# fri3d_badge_2016.net
KiCad netlist of a schematic drawn in EAGLE
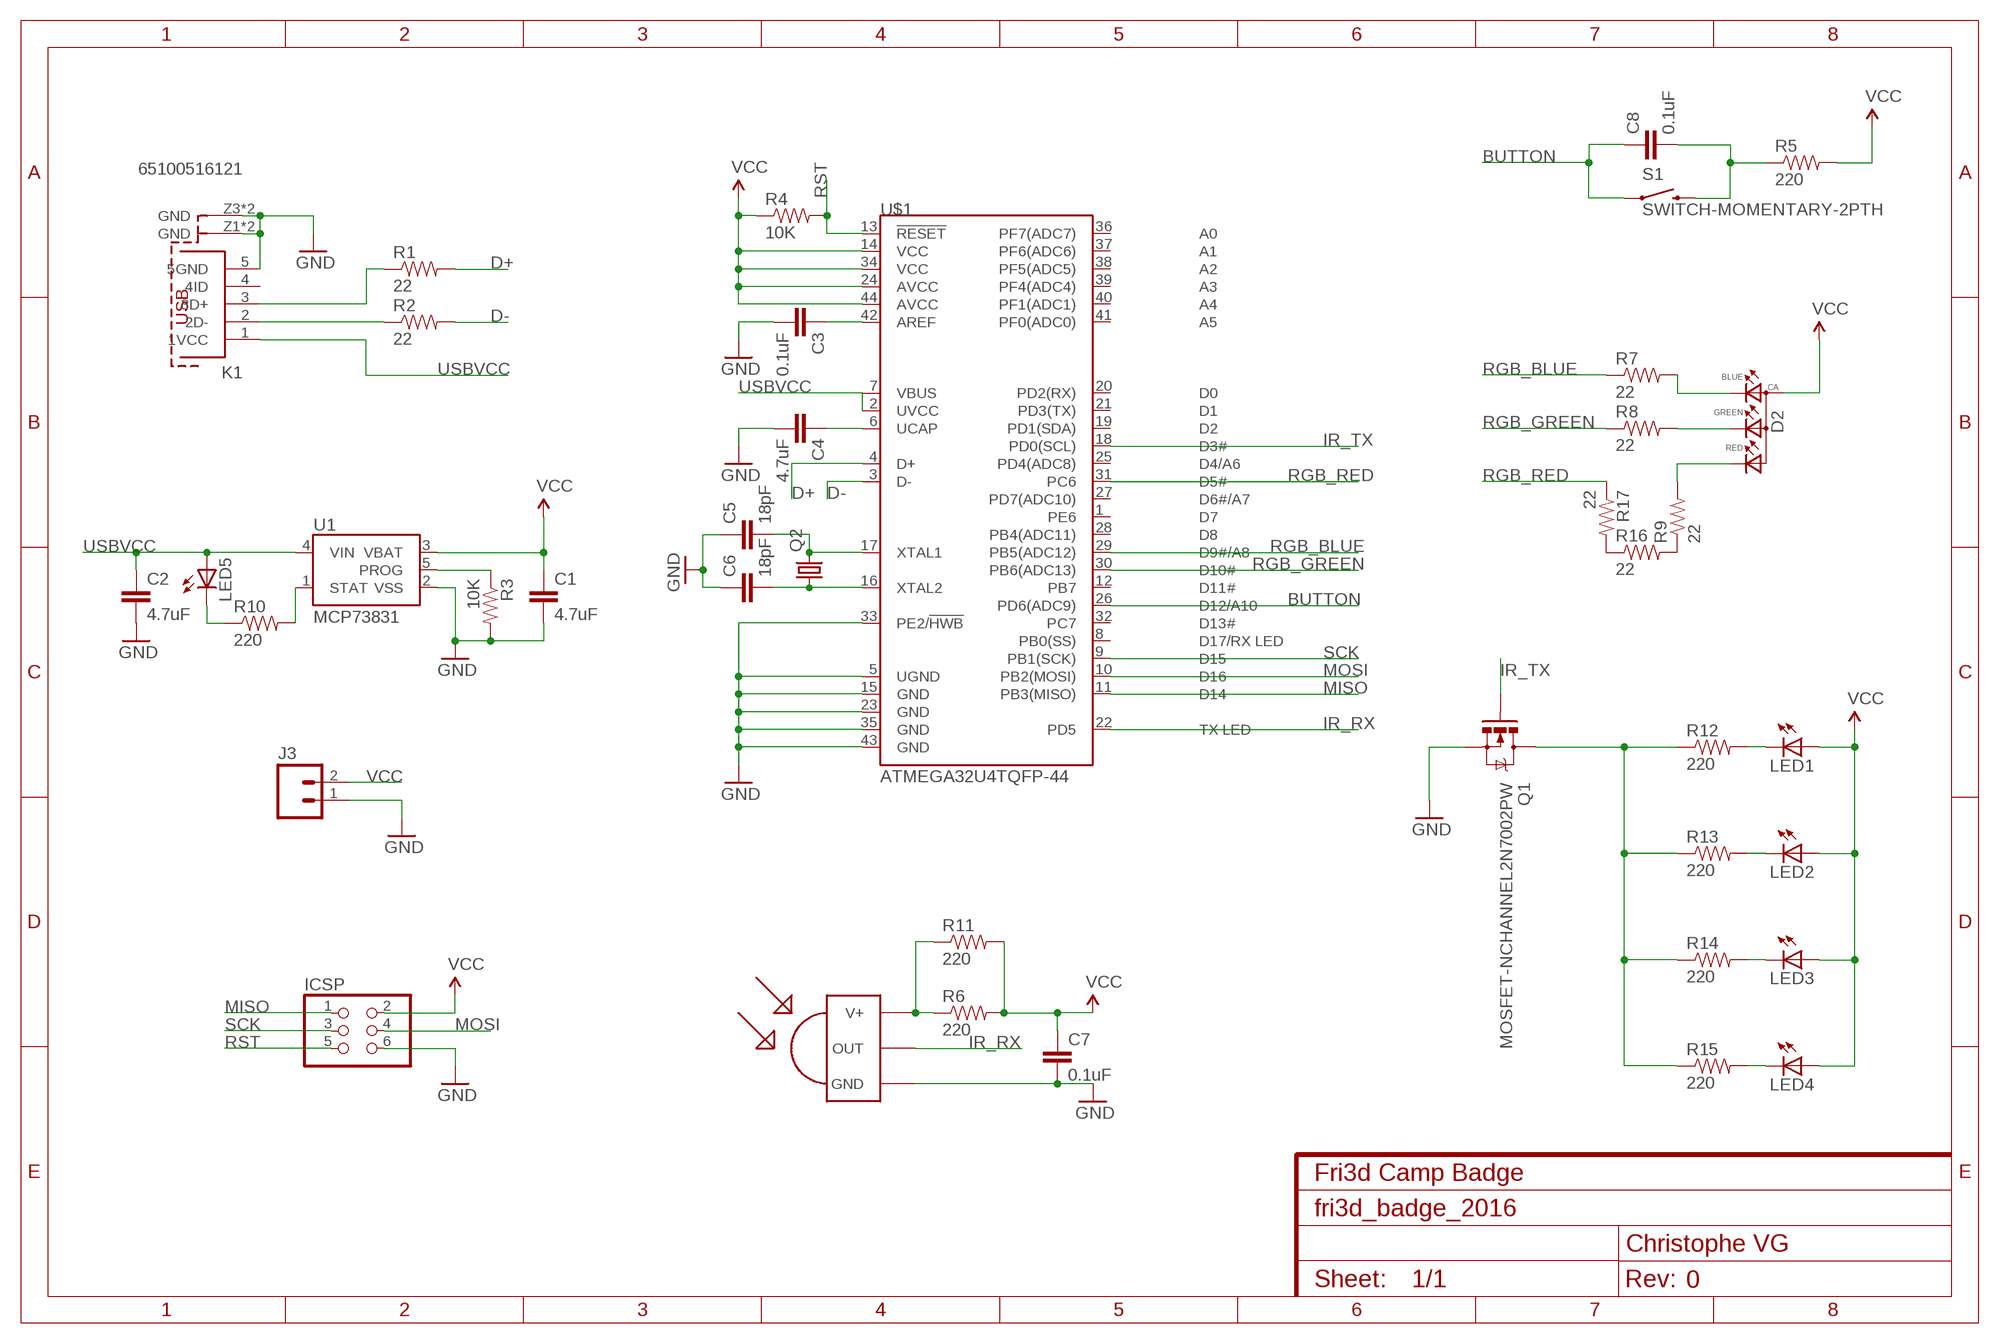
[diagram p0: schematic, sheet 1]

(export (version "E")
  (design (tool "Eeschema 10.0.6"))
  (components
    (comp (ref "C1")
      (value "4.7uF")
      (footprint "eagle-import:0805")
      (libsource (lib "eagle-import") (part "CAP0805"))
    )
    (comp (ref "C2")
      (value "4.7uF")
      (footprint "eagle-import:0805")
      (libsource (lib "eagle-import") (part "CAP0805"))
    )
    (comp (ref "C3")
      (value "0.1uF")
      (footprint "eagle-import:0805")
      (libsource (lib "eagle-import") (part "CAP0805"))
    )
    (comp (ref "C4")
      (value "4.7uF")
      (footprint "eagle-import:0805")
      (libsource (lib "eagle-import") (part "CAP0805"))
    )
    (comp (ref "C5")
      (value "18pF")
      (footprint "eagle-import:0805")
      (libsource (lib "eagle-import") (part "CAP0805"))
    )
    (comp (ref "C6")
      (value "18pF")
      (footprint "eagle-import:0805")
      (libsource (lib "eagle-import") (part "CAP0805"))
    )
    (comp (ref "C7")
      (value "0.1uF")
      (footprint "eagle-import:0805")
      (libsource (lib "eagle-import") (part "CAP0805"))
    )
    (comp (ref "C8")
      (value "0.1uF")
      (footprint "eagle-import:0805")
      (libsource (lib "eagle-import") (part "CAP0805"))
    )
    (comp (ref "D2")
      (value "0.13_RGB_LEDPLCC")
      (footprint "eagle-import:P-LCC-4-3")
      (libsource (lib "eagle-import") (part "0.13_RGB_LEDPLCC"))
    )
    (comp (ref "ICSP")
      (value "PINHD-2X3")
      (footprint "eagle-import:2X03")
      (libsource (lib "eagle-import") (part "PINHD-2X3"))
    )
    (comp (ref "J3")
      (value "M02JST-PTH-VERT")
      (footprint "eagle-import:JST-2-PTH-VERT")
      (libsource (lib "eagle-import") (part "M02JST-PTH-VERT"))
    )
    (comp (ref "K1")
      (value "65100516121")
      (footprint "eagle-import:65100516121")
      (libsource (lib "eagle-import") (part "65100516121"))
    )
    (comp (ref "LED1")
      (value "LEDCHIPLED_0805")
      (footprint "eagle-import:CHIPLED_0805")
      (libsource (lib "eagle-import") (part "led_LEDCHIPLED_0805"))
    )
    (comp (ref "LED2")
      (value "LEDCHIPLED_0805")
      (footprint "eagle-import:CHIPLED_0805")
      (libsource (lib "eagle-import") (part "led_LEDCHIPLED_0805"))
    )
    (comp (ref "LED3")
      (value "LEDCHIPLED_0805")
      (footprint "eagle-import:CHIPLED_0805")
      (libsource (lib "eagle-import") (part "led_LEDCHIPLED_0805"))
    )
    (comp (ref "LED4")
      (value "LEDCHIPLED_0805")
      (footprint "eagle-import:CHIPLED_0805")
      (libsource (lib "eagle-import") (part "led_LEDCHIPLED_0805"))
    )
    (comp (ref "LED5")
      (value "LEDCHIPLED_0805")
      (footprint "eagle-import:CHIPLED_0805")
      (libsource (lib "eagle-import") (part "LEDCHIPLED_0805"))
    )
    (comp (ref "Q1")
      (value "MOSFET-NCHANNEL2N7002PW")
      (footprint "eagle-import:SOT323")
      (libsource (lib "eagle-import") (part "MOSFET-NCHANNEL2N7002PW"))
    )
    (comp (ref "Q2")
      (value "CRYSTALHC49S")
      (footprint "eagle-import:HC49_S")
      (libsource (lib "eagle-import") (part "CRYSTALHC49S"))
    )
    (comp (ref "R1")
      (value "22")
      (footprint "eagle-import:0805")
      (libsource (lib "eagle-import") (part "RESISTOR0805-RES"))
    )
    (comp (ref "R2")
      (value "22")
      (footprint "eagle-import:0805")
      (libsource (lib "eagle-import") (part "RESISTOR0805-RES"))
    )
    (comp (ref "R3")
      (value "10K")
      (footprint "eagle-import:0805")
      (libsource (lib "eagle-import") (part "RESISTOR0805-RES"))
    )
    (comp (ref "R4")
      (value "10K")
      (footprint "eagle-import:0805")
      (libsource (lib "eagle-import") (part "RESISTOR0805-RES"))
    )
    (comp (ref "R5")
      (value "220")
      (footprint "eagle-import:0805")
      (libsource (lib "eagle-import") (part "RESISTOR0805-RES"))
    )
    (comp (ref "R6")
      (value "220")
      (footprint "eagle-import:0805")
      (libsource (lib "eagle-import") (part "RESISTOR0805-RES"))
    )
    (comp (ref "R7")
      (value "22")
      (footprint "eagle-import:0805")
      (libsource (lib "eagle-import") (part "RESISTOR0805-RES"))
    )
    (comp (ref "R8")
      (value "22")
      (footprint "eagle-import:0805")
      (libsource (lib "eagle-import") (part "RESISTOR0805-RES"))
    )
    (comp (ref "R9")
      (value "22")
      (footprint "eagle-import:0805")
      (libsource (lib "eagle-import") (part "RESISTOR0805-RES"))
    )
    (comp (ref "R10")
      (value "220")
      (footprint "eagle-import:0805")
      (libsource (lib "eagle-import") (part "RESISTOR0805-RES"))
    )
    (comp (ref "R11")
      (value "220")
      (footprint "eagle-import:0805")
      (libsource (lib "eagle-import") (part "RESISTOR0805-RES"))
    )
    (comp (ref "R12")
      (value "220")
      (footprint "eagle-import:0805")
      (libsource (lib "eagle-import") (part "RESISTOR0805-RES"))
    )
    (comp (ref "R13")
      (value "220")
      (footprint "eagle-import:0805")
      (libsource (lib "eagle-import") (part "RESISTOR0805-RES"))
    )
    (comp (ref "R14")
      (value "220")
      (footprint "eagle-import:0805")
      (libsource (lib "eagle-import") (part "RESISTOR0805-RES"))
    )
    (comp (ref "R15")
      (value "220")
      (footprint "eagle-import:0805")
      (libsource (lib "eagle-import") (part "RESISTOR0805-RES"))
    )
    (comp (ref "R16")
      (value "22")
      (footprint "eagle-import:0805")
      (libsource (lib "eagle-import") (part "RESISTOR0805-RES"))
    )
    (comp (ref "R17")
      (value "22")
      (footprint "eagle-import:0805")
      (libsource (lib "eagle-import") (part "RESISTOR0805-RES"))
    )
    (comp (ref "S1")
      (value "SWITCH-MOMENTARY-2PTH")
      (footprint "eagle-import:TACTILE-PTH")
      (libsource (lib "eagle-import") (part "SWITCH-MOMENTARY-2PTH"))
    )
    (comp (ref "U$1")
      (value "ATMEGA32U4TQFP-44")
      (footprint "eagle-import:TQFP44")
      (libsource (lib "eagle-import") (part "ATMEGA32U4TQFP-44"))
    )
    (comp (ref "U$3")
      (value "TSOP4838")
      (footprint "eagle-import:TSOP18XX")
      (libsource (lib "eagle-import") (part "TSOP4838"))
    )
    (comp (ref "U1")
      (value "MCP73831")
      (footprint "eagle-import:SOT23-5")
      (libsource (lib "eagle-import") (part "MCP73831"))
    )
  )
  (nets
    (net (code "1") (name "/BUTTON") (class "Default")
      (node (ref "C8") (pin "1") (pinfunction "1_1") (pintype "passive"))
      (node (ref "S1") (pin "1") (pinfunction "1_1") (pintype "passive"))
      (node (ref "U$1") (pin "26") (pinfunction "PD6(ADC9)_26") (pintype "bidirectional"))
    )
    (net (code "2") (name "/D+") (class "Default")
      (node (ref "R1") (pin "2") (pinfunction "2_2") (pintype "passive"))
      (node (ref "U$1") (pin "4") (pinfunction "D+_4") (pintype "bidirectional"))
    )
    (net (code "3") (name "/D-") (class "Default")
      (node (ref "R2") (pin "2") (pinfunction "2_2") (pintype "passive"))
      (node (ref "U$1") (pin "3") (pinfunction "D-_3") (pintype "bidirectional"))
    )
    (net (code "4") (name "/IR_RX") (class "Default")
      (node (ref "U$1") (pin "22") (pinfunction "PD5_22") (pintype "bidirectional"))
      (node (ref "U$3") (pin "OUT") (pinfunction "OUT_OUT") (pintype "bidirectional"))
    )
    (net (code "5") (name "/IR_TX") (class "Default")
      (node (ref "Q1") (pin "1") (pinfunction "G_1") (pintype "passive"))
      (node (ref "U$1") (pin "18") (pinfunction "PD0(SCL)_18") (pintype "bidirectional"))
    )
    (net (code "6") (name "/MISO") (class "Default")
      (node (ref "ICSP") (pin "1") (pinfunction "1_1") (pintype "passive"))
      (node (ref "U$1") (pin "11") (pinfunction "PB3(MISO)_11") (pintype "bidirectional"))
    )
    (net (code "7") (name "/MOSI") (class "Default")
      (node (ref "ICSP") (pin "4") (pinfunction "4_4") (pintype "passive"))
      (node (ref "U$1") (pin "10") (pinfunction "PB2(MOSI)_10") (pintype "bidirectional"))
    )
    (net (code "8") (name "/RGB_BLUE") (class "Default")
      (node (ref "R7") (pin "1") (pinfunction "1_1") (pintype "passive"))
      (node (ref "U$1") (pin "29") (pinfunction "PB5(ADC12)_29") (pintype "bidirectional"))
    )
    (net (code "9") (name "/RGB_GREEN") (class "Default")
      (node (ref "R8") (pin "1") (pinfunction "1_1") (pintype "passive"))
      (node (ref "U$1") (pin "30") (pinfunction "PB6(ADC13)_30") (pintype "bidirectional"))
    )
    (net (code "10") (name "/RGB_RED") (class "Default")
      (node (ref "R17") (pin "1") (pinfunction "1_1") (pintype "passive"))
      (node (ref "U$1") (pin "31") (pinfunction "PC6_31") (pintype "bidirectional"))
    )
    (net (code "11") (name "/RST") (class "Default")
      (node (ref "ICSP") (pin "5") (pinfunction "5_5") (pintype "passive"))
      (node (ref "R4") (pin "2") (pinfunction "2_2") (pintype "passive"))
      (node (ref "U$1") (pin "13") (pinfunction "~{RESET}_13") (pintype "bidirectional"))
    )
    (net (code "12") (name "/SCK") (class "Default")
      (node (ref "ICSP") (pin "3") (pinfunction "3_3") (pintype "passive"))
      (node (ref "U$1") (pin "9") (pinfunction "PB1(SCK)_9") (pintype "bidirectional"))
    )
    (net (code "13") (name "/USBVCC") (class "Default")
      (node (ref "C2") (pin "1") (pinfunction "1_1") (pintype "passive"))
      (node (ref "K1") (pin "1") (pinfunction "1VCC_1") (pintype "passive"))
      (node (ref "LED5") (pin "A") (pinfunction "A_A") (pintype "passive"))
      (node (ref "U$1") (pin "2") (pinfunction "UVCC_2") (pintype "bidirectional"))
      (node (ref "U$1") (pin "7") (pinfunction "VBUS_7") (pintype "bidirectional"))
      (node (ref "U1") (pin "4") (pinfunction "VIN_4") (pintype "power_in"))
    )
    (net (code "14") (name "GND") (class "Default")
      (node (ref "C1") (pin "2") (pinfunction "2_2") (pintype "passive"))
      (node (ref "C2") (pin "2") (pinfunction "2_2") (pintype "passive"))
      (node (ref "C3") (pin "2") (pinfunction "2_2") (pintype "passive"))
      (node (ref "C4") (pin "2") (pinfunction "2_2") (pintype "passive"))
      (node (ref "C5") (pin "1") (pinfunction "1_1") (pintype "passive"))
      (node (ref "C6") (pin "1") (pinfunction "1_1") (pintype "passive"))
      (node (ref "C7") (pin "2") (pinfunction "2_2") (pintype "passive"))
      (node (ref "ICSP") (pin "6") (pinfunction "6_6") (pintype "passive"))
      (node (ref "J3") (pin "1") (pinfunction "1_1") (pintype "passive"))
      (node (ref "K1") (pin "5") (pinfunction "5GND_5") (pintype "passive"))
      (node (ref "K1") (pin "Z1") (pinfunction "GND_Z1") (pintype "bidirectional"))
      (node (ref "K1") (pin "Z2") (pinfunction "GND_Z2") (pintype "bidirectional"))
      (node (ref "K1") (pin "Z3") (pinfunction "GND_Z3") (pintype "bidirectional"))
      (node (ref "K1") (pin "Z4") (pinfunction "GND_Z4") (pintype "bidirectional"))
      (node (ref "Q1") (pin "2") (pinfunction "S_2") (pintype "passive"))
      (node (ref "R3") (pin "2") (pinfunction "2_2") (pintype "passive"))
      (node (ref "U$1") (pin "15") (pinfunction "GND_15") (pintype "bidirectional"))
      (node (ref "U$1") (pin "23") (pinfunction "GND_23") (pintype "bidirectional"))
      (node (ref "U$1") (pin "33") (pinfunction "PE2/~{HWB}_33") (pintype "bidirectional"))
      (node (ref "U$1") (pin "35") (pinfunction "GND_35") (pintype "bidirectional"))
      (node (ref "U$1") (pin "43") (pinfunction "GND_43") (pintype "bidirectional"))
      (node (ref "U$1") (pin "5") (pinfunction "UGND_5") (pintype "bidirectional"))
      (node (ref "U$3") (pin "GND") (pinfunction "GND_GND") (pintype "bidirectional"))
      (node (ref "U1") (pin "2") (pinfunction "VSS_2") (pintype "power_in"))
    )
    (net (code "15") (name "Net-(D2-BLUE)") (class "Default")
      (node (ref "D2") (pin "3") (pinfunction "BLUE_3") (pintype "passive"))
      (node (ref "R7") (pin "2") (pinfunction "2_2") (pintype "passive"))
    )
    (net (code "16") (name "Net-(D2-GREEN)") (class "Default")
      (node (ref "D2") (pin "2") (pinfunction "GREEN_2") (pintype "passive"))
      (node (ref "R8") (pin "2") (pinfunction "2_2") (pintype "passive"))
    )
    (net (code "17") (name "Net-(D2-RED)") (class "Default")
      (node (ref "D2") (pin "1") (pinfunction "RED_1") (pintype "passive"))
      (node (ref "R9") (pin "2") (pinfunction "2_2") (pintype "passive"))
    )
    (net (code "18") (name "Net-(K1-2D-)") (class "Default")
      (node (ref "K1") (pin "2") (pinfunction "2D-_2") (pintype "passive"))
      (node (ref "R2") (pin "1") (pinfunction "1_1") (pintype "passive"))
    )
    (net (code "19") (name "Net-(K1-3D+)") (class "Default")
      (node (ref "K1") (pin "3") (pinfunction "3D+_3") (pintype "passive"))
      (node (ref "R1") (pin "1") (pinfunction "1_1") (pintype "passive"))
    )
    (net (code "20") (name "Net-(LED1-PadC)") (class "Default")
      (node (ref "LED1") (pin "C") (pinfunction "C_C") (pintype "passive"))
      (node (ref "R12") (pin "2") (pinfunction "2_2") (pintype "passive"))
    )
    (net (code "21") (name "Net-(LED2-PadC)") (class "Default")
      (node (ref "LED2") (pin "C") (pinfunction "C_C") (pintype "passive"))
      (node (ref "R13") (pin "2") (pinfunction "2_2") (pintype "passive"))
    )
    (net (code "22") (name "Net-(LED3-PadC)") (class "Default")
      (node (ref "LED3") (pin "C") (pinfunction "C_C") (pintype "passive"))
      (node (ref "R14") (pin "2") (pinfunction "2_2") (pintype "passive"))
    )
    (net (code "23") (name "Net-(LED4-PadC)") (class "Default")
      (node (ref "LED4") (pin "C") (pinfunction "C_C") (pintype "passive"))
      (node (ref "R15") (pin "2") (pinfunction "2_2") (pintype "passive"))
    )
    (net (code "24") (name "Net-(LED5-PadC)") (class "Default")
      (node (ref "LED5") (pin "C") (pinfunction "C_C") (pintype "passive"))
      (node (ref "R10") (pin "1") (pinfunction "1_1") (pintype "passive"))
    )
    (net (code "25") (name "Net-(Q1-D)") (class "Default")
      (node (ref "Q1") (pin "3") (pinfunction "D_3") (pintype "passive"))
      (node (ref "R12") (pin "1") (pinfunction "1_1") (pintype "passive"))
      (node (ref "R13") (pin "1") (pinfunction "1_1") (pintype "passive"))
      (node (ref "R14") (pin "1") (pinfunction "1_1") (pintype "passive"))
      (node (ref "R15") (pin "1") (pinfunction "1_1") (pintype "passive"))
    )
    (net (code "26") (name "Net-(R16-Pad1)") (class "Default")
      (node (ref "R16") (pin "1") (pinfunction "1_1") (pintype "passive"))
      (node (ref "R17") (pin "2") (pinfunction "2_2") (pintype "passive"))
    )
    (net (code "27") (name "Net-(R16-Pad2)") (class "Default")
      (node (ref "R16") (pin "2") (pinfunction "2_2") (pintype "passive"))
      (node (ref "R9") (pin "1") (pinfunction "1_1") (pintype "passive"))
    )
    (net (code "28") (name "Net-(S1-2)") (class "Default")
      (node (ref "C8") (pin "2") (pinfunction "2_2") (pintype "passive"))
      (node (ref "R5") (pin "1") (pinfunction "1_1") (pintype "passive"))
      (node (ref "S1") (pin "3") (pinfunction "2_3") (pintype "passive"))
    )
    (net (code "29") (name "Net-(U$1-AREF)") (class "Default")
      (node (ref "C3") (pin "1") (pinfunction "1_1") (pintype "passive"))
      (node (ref "U$1") (pin "42") (pinfunction "AREF_42") (pintype "bidirectional"))
    )
    (net (code "30") (name "Net-(U$1-UCAP)") (class "Default")
      (node (ref "C4") (pin "1") (pinfunction "1_1") (pintype "passive"))
      (node (ref "U$1") (pin "6") (pinfunction "UCAP_6") (pintype "bidirectional"))
    )
    (net (code "31") (name "Net-(U$1-XTAL1)") (class "Default")
      (node (ref "C5") (pin "2") (pinfunction "2_2") (pintype "passive"))
      (node (ref "Q2") (pin "2") (pinfunction "2_2") (pintype "passive"))
      (node (ref "U$1") (pin "17") (pinfunction "XTAL1_17") (pintype "bidirectional"))
    )
    (net (code "32") (name "Net-(U$1-XTAL2)") (class "Default")
      (node (ref "C6") (pin "2") (pinfunction "2_2") (pintype "passive"))
      (node (ref "Q2") (pin "1") (pinfunction "1_1") (pintype "passive"))
      (node (ref "U$1") (pin "16") (pinfunction "XTAL2_16") (pintype "bidirectional"))
    )
    (net (code "33") (name "Net-(U$3-V+)") (class "Default")
      (node (ref "R11") (pin "1") (pinfunction "1_1") (pintype "passive"))
      (node (ref "R6") (pin "1") (pinfunction "1_1") (pintype "passive"))
      (node (ref "U$3") (pin "VCC") (pinfunction "V+_VCC") (pintype "bidirectional"))
    )
    (net (code "34") (name "Net-(U1-PROG)") (class "Default")
      (node (ref "R3") (pin "1") (pinfunction "1_1") (pintype "passive"))
      (node (ref "U1") (pin "5") (pinfunction "PROG_5") (pintype "input"))
    )
    (net (code "35") (name "Net-(U1-STAT)") (class "Default")
      (node (ref "R10") (pin "2") (pinfunction "2_2") (pintype "passive"))
      (node (ref "U1") (pin "1") (pinfunction "STAT_1") (pintype "output"))
    )
    (net (code "36") (name "VCC") (class "Default")
      (node (ref "C1") (pin "1") (pinfunction "1_1") (pintype "passive"))
      (node (ref "C7") (pin "1") (pinfunction "1_1") (pintype "passive"))
      (node (ref "D2") (pin "4") (pinfunction "ANODE_4") (pintype "passive"))
      (node (ref "ICSP") (pin "2") (pinfunction "2_2") (pintype "passive"))
      (node (ref "J3") (pin "2") (pinfunction "2_2") (pintype "passive"))
      (node (ref "LED1") (pin "A") (pinfunction "A_A") (pintype "passive"))
      (node (ref "LED2") (pin "A") (pinfunction "A_A") (pintype "passive"))
      (node (ref "LED3") (pin "A") (pinfunction "A_A") (pintype "passive"))
      (node (ref "LED4") (pin "A") (pinfunction "A_A") (pintype "passive"))
      (node (ref "R11") (pin "2") (pinfunction "2_2") (pintype "passive"))
      (node (ref "R4") (pin "1") (pinfunction "1_1") (pintype "passive"))
      (node (ref "R5") (pin "2") (pinfunction "2_2") (pintype "passive"))
      (node (ref "R6") (pin "2") (pinfunction "2_2") (pintype "passive"))
      (node (ref "U$1") (pin "14") (pinfunction "VCC_14") (pintype "bidirectional"))
      (node (ref "U$1") (pin "24") (pinfunction "AVCC_24") (pintype "bidirectional"))
      (node (ref "U$1") (pin "34") (pinfunction "VCC_34") (pintype "bidirectional"))
      (node (ref "U$1") (pin "44") (pinfunction "AVCC_44") (pintype "bidirectional"))
      (node (ref "U1") (pin "3") (pinfunction "VBAT_3") (pintype "power_in"))
    )
    (net (code "37") (name "unconnected-(K1-4ID-Pad4)") (class "Default")
      (node (ref "K1") (pin "4") (pinfunction "4ID_4") (pintype "passive"))
    )
    (net (code "38") (name "unconnected-(U$1-PB0(SS)-Pad8)") (class "Default")
      (node (ref "U$1") (pin "8") (pinfunction "PB0(SS)_8") (pintype "bidirectional"))
    )
    (net (code "39") (name "unconnected-(U$1-PB4(ADC11)-Pad28)") (class "Default")
      (node (ref "U$1") (pin "28") (pinfunction "PB4(ADC11)_28") (pintype "bidirectional"))
    )
    (net (code "40") (name "unconnected-(U$1-PB7-Pad12)") (class "Default")
      (node (ref "U$1") (pin "12") (pinfunction "PB7_12") (pintype "bidirectional"))
    )
    (net (code "41") (name "unconnected-(U$1-PC7-Pad32)") (class "Default")
      (node (ref "U$1") (pin "32") (pinfunction "PC7_32") (pintype "bidirectional"))
    )
    (net (code "42") (name "unconnected-(U$1-PD1(SDA)-Pad19)") (class "Default")
      (node (ref "U$1") (pin "19") (pinfunction "PD1(SDA)_19") (pintype "bidirectional"))
    )
    (net (code "43") (name "unconnected-(U$1-PD2(RX)-Pad20)") (class "Default")
      (node (ref "U$1") (pin "20") (pinfunction "PD2(RX)_20") (pintype "bidirectional"))
    )
    (net (code "44") (name "unconnected-(U$1-PD3(TX)-Pad21)") (class "Default")
      (node (ref "U$1") (pin "21") (pinfunction "PD3(TX)_21") (pintype "bidirectional"))
    )
    (net (code "45") (name "unconnected-(U$1-PD4(ADC8)-Pad25)") (class "Default")
      (node (ref "U$1") (pin "25") (pinfunction "PD4(ADC8)_25") (pintype "bidirectional"))
    )
    (net (code "46") (name "unconnected-(U$1-PD7(ADC10)-Pad27)") (class "Default")
      (node (ref "U$1") (pin "27") (pinfunction "PD7(ADC10)_27") (pintype "bidirectional"))
    )
    (net (code "47") (name "unconnected-(U$1-PE6-Pad1)") (class "Default")
      (node (ref "U$1") (pin "1") (pinfunction "PE6_1") (pintype "bidirectional"))
    )
    (net (code "48") (name "unconnected-(U$1-PF0(ADC0)-Pad41)") (class "Default")
      (node (ref "U$1") (pin "41") (pinfunction "PF0(ADC0)_41") (pintype "bidirectional"))
    )
    (net (code "49") (name "unconnected-(U$1-PF1(ADC1)-Pad40)") (class "Default")
      (node (ref "U$1") (pin "40") (pinfunction "PF1(ADC1)_40") (pintype "bidirectional"))
    )
    (net (code "50") (name "unconnected-(U$1-PF4(ADC4)-Pad39)") (class "Default")
      (node (ref "U$1") (pin "39") (pinfunction "PF4(ADC4)_39") (pintype "bidirectional"))
    )
    (net (code "51") (name "unconnected-(U$1-PF5(ADC5)-Pad38)") (class "Default")
      (node (ref "U$1") (pin "38") (pinfunction "PF5(ADC5)_38") (pintype "bidirectional"))
    )
    (net (code "52") (name "unconnected-(U$1-PF6(ADC6)-Pad37)") (class "Default")
      (node (ref "U$1") (pin "37") (pinfunction "PF6(ADC6)_37") (pintype "bidirectional"))
    )
    (net (code "53") (name "unconnected-(U$1-PF7(ADC7)-Pad36)") (class "Default")
      (node (ref "U$1") (pin "36") (pinfunction "PF7(ADC7)_36") (pintype "bidirectional"))
    )
  )
)
